# led_ext_board.net
KiCad netlist of a schematic drawn in Altium Designer
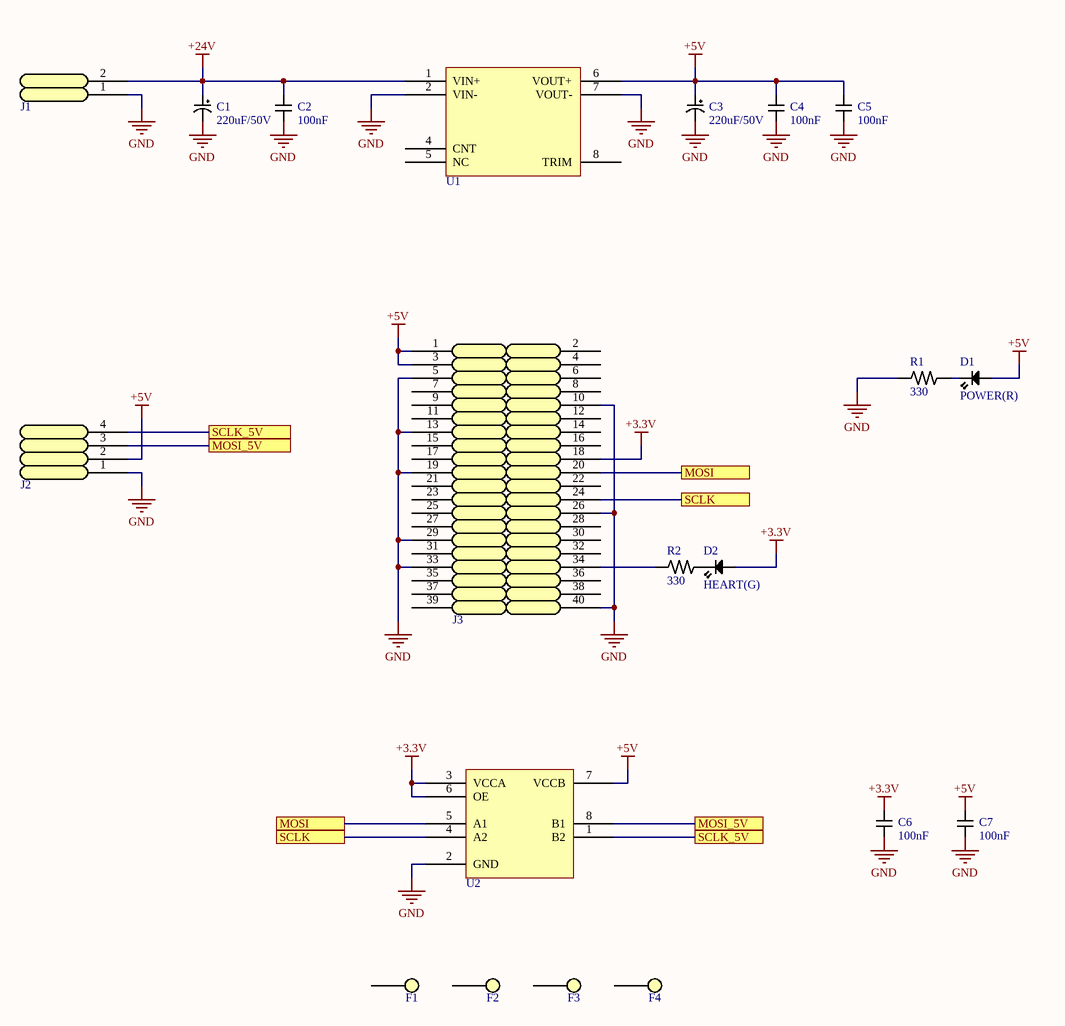
[diagram p0: led_ext_board.SchDoc]

(export (version "E")
  (design (tool "Eeschema 10.0.6"))
  (components
    (comp (ref "C1")
      (value "220uF/50V")
      (footprint "EC-J10-10X10")
      (description "Polarized Capacitor")
      (fields (field (name "Comment") "EC"))
      (libsource (lib "led_ext_board") (part "EC"))
    )
    (comp (ref "C2")
      (value "100nF")
      (footprint "CAP1608L")
      (description "Non-polarized Capacitor")
      (fields (field (name "Comment") "C"))
      (libsource (lib "led_ext_board") (part "C"))
    )
    (comp (ref "C3")
      (value "220uF/50V")
      (footprint "EC-J10-10X10")
      (description "Polarized Capacitor")
      (fields (field (name "Comment") "EC"))
      (libsource (lib "led_ext_board") (part "EC"))
    )
    (comp (ref "C4")
      (value "100nF")
      (footprint "CAP1608L")
      (description "Non-polarized Capacitor")
      (fields (field (name "Comment") "C"))
      (libsource (lib "led_ext_board") (part "C"))
    )
    (comp (ref "C5")
      (value "100nF")
      (footprint "CAP1608L")
      (description "Non-polarized Capacitor")
      (fields (field (name "Comment") "C"))
      (libsource (lib "led_ext_board") (part "C"))
    )
    (comp (ref "C6")
      (value "100nF")
      (footprint "CAP1608L")
      (description "Non-polarized Capacitor")
      (fields (field (name "Comment") "C"))
      (libsource (lib "led_ext_board") (part "C"))
    )
    (comp (ref "C7")
      (value "100nF")
      (footprint "CAP1608L")
      (description "Non-polarized Capacitor")
      (fields (field (name "Comment") "C"))
      (libsource (lib "led_ext_board") (part "C"))
    )
    (comp (ref "D1")
      (value "POWER(R)")
      (footprint "LED1608L")
      (description "Typical LED")
      (fields (field (name "Comment") "LED"))
      (libsource (lib "led_ext_board") (part "LED"))
    )
    (comp (ref "D2")
      (value "HEART(G)")
      (footprint "LED1608L")
      (description "Typical LED")
      (fields (field (name "Comment") "LED"))
      (libsource (lib "led_ext_board") (part "LED"))
    )
    (comp (ref "F1")
      (value "FIXED_HOLE")
      (footprint "FIXED_HOLE_PAD")
      (libsource (lib "led_ext_board") (part "FIXED_HOLE"))
    )
    (comp (ref "F2")
      (value "FIXED_HOLE")
      (footprint "FIXED_HOLE_PAD")
      (libsource (lib "led_ext_board") (part "FIXED_HOLE"))
    )
    (comp (ref "F3")
      (value "FIXED_HOLE")
      (footprint "FIXED_HOLE_PAD")
      (libsource (lib "led_ext_board") (part "FIXED_HOLE"))
    )
    (comp (ref "F4")
      (value "FIXED_HOLE")
      (footprint "FIXED_HOLE_PAD")
      (libsource (lib "led_ext_board") (part "FIXED_HOLE"))
    )
    (comp (ref "J1")
      (value "CON2")
      (footprint "DG128-5.0-02P")
      (libsource (lib "led_ext_board") (part "CON2"))
    )
    (comp (ref "J2")
      (value "CON4")
      (footprint "DG128-5.0-04P")
      (description "Generic Connector 4 Pin")
      (libsource (lib "led_ext_board") (part "CON4"))
    )
    (comp (ref "J3")
      (value "CON2X20")
      (footprint "HS-2X20-2.54-V")
      (description "Generic Connector 2X20")
      (libsource (lib "led_ext_board") (part "CON2X20"))
    )
    (comp (ref "R1")
      (value "330")
      (footprint "RES1608L")
      (description "Resistor")
      (fields (field (name "Comment") "R"))
      (libsource (lib "led_ext_board") (part "R"))
    )
    (comp (ref "R2")
      (value "330")
      (footprint "RES1608L")
      (description "Resistor")
      (fields (field (name "Comment") "R"))
      (libsource (lib "led_ext_board") (part "R"))
    )
    (comp (ref "U1")
      (value "PBR50 Series DC-DC Converter")
      (footprint "PBR50-24-5")
      (libsource (lib "led_ext_board") (part "PBR50"))
    )
    (comp (ref "U2")
      (value "TXB0102")
      (footprint "TXB0102")
      (libsource (lib "led_ext_board") (part "TXB0102"))
    )
  )
  (nets
    (net (code "1") (name "+3.3V") (class "Default")
      (node (ref "C6") (pin "1") (pinfunction "1_1") (pintype "passive"))
      (node (ref "D2") (pin "2") (pinfunction "2_2") (pintype "passive"))
      (node (ref "J3") (pin "18") (pinfunction "18_18") (pintype "passive"))
      (node (ref "U2") (pin "3") (pinfunction "VCCA_3") (pintype "passive"))
      (node (ref "U2") (pin "6") (pinfunction "OE_6") (pintype "passive"))
    )
    (net (code "2") (name "+5V") (class "Default")
      (node (ref "C3") (pin "1") (pinfunction "1_1") (pintype "passive"))
      (node (ref "C4") (pin "1") (pinfunction "1_1") (pintype "passive"))
      (node (ref "C5") (pin "1") (pinfunction "1_1") (pintype "passive"))
      (node (ref "C7") (pin "1") (pinfunction "1_1") (pintype "passive"))
      (node (ref "D1") (pin "2") (pinfunction "2_2") (pintype "passive"))
      (node (ref "J2") (pin "2") (pinfunction "2_2") (pintype "passive"))
      (node (ref "J3") (pin "1") (pinfunction "1_1") (pintype "passive"))
      (node (ref "J3") (pin "3") (pinfunction "3_3") (pintype "passive"))
      (node (ref "U1") (pin "6") (pinfunction "VOUT+_6") (pintype "passive"))
      (node (ref "U2") (pin "7") (pinfunction "VCCB_7") (pintype "passive"))
    )
    (net (code "3") (name "+24V") (class "Default")
      (node (ref "C1") (pin "1") (pinfunction "1_1") (pintype "passive"))
      (node (ref "C2") (pin "1") (pinfunction "1_1") (pintype "passive"))
      (node (ref "J1") (pin "2") (pinfunction "2_2") (pintype "passive"))
      (node (ref "U1") (pin "1") (pinfunction "VIN+_1") (pintype "passive"))
    )
    (net (code "4") (name "/MOSI") (class "Default")
      (node (ref "J3") (pin "20") (pinfunction "20_20") (pintype "passive"))
      (node (ref "U2") (pin "5") (pinfunction "A1_5") (pintype "passive"))
    )
    (net (code "5") (name "/MOSI_5V") (class "Default")
      (node (ref "J2") (pin "3") (pinfunction "3_3") (pintype "passive"))
      (node (ref "U2") (pin "8") (pinfunction "B1_8") (pintype "passive"))
    )
    (net (code "6") (name "/SCLK") (class "Default")
      (node (ref "J3") (pin "24") (pinfunction "24_24") (pintype "passive"))
      (node (ref "U2") (pin "4") (pinfunction "A2_4") (pintype "passive"))
    )
    (net (code "7") (name "/SCLK_5V") (class "Default")
      (node (ref "J2") (pin "4") (pinfunction "4_4") (pintype "passive"))
      (node (ref "U2") (pin "1") (pinfunction "B2_1") (pintype "passive"))
    )
    (net (code "8") (name "GND") (class "Default")
      (node (ref "C1") (pin "2") (pinfunction "2_2") (pintype "passive"))
      (node (ref "C2") (pin "2") (pinfunction "2_2") (pintype "passive"))
      (node (ref "C3") (pin "2") (pinfunction "2_2") (pintype "passive"))
      (node (ref "C4") (pin "2") (pinfunction "2_2") (pintype "passive"))
      (node (ref "C5") (pin "2") (pinfunction "2_2") (pintype "passive"))
      (node (ref "C6") (pin "2") (pinfunction "2_2") (pintype "passive"))
      (node (ref "C7") (pin "2") (pinfunction "2_2") (pintype "passive"))
      (node (ref "J1") (pin "1") (pinfunction "1_1") (pintype "passive"))
      (node (ref "J2") (pin "1") (pinfunction "1_1") (pintype "passive"))
      (node (ref "J3") (pin "10") (pinfunction "10_10") (pintype "passive"))
      (node (ref "J3") (pin "13") (pinfunction "13_13") (pintype "passive"))
      (node (ref "J3") (pin "19") (pinfunction "19_19") (pintype "passive"))
      (node (ref "J3") (pin "26") (pinfunction "26_26") (pintype "passive"))
      (node (ref "J3") (pin "29") (pinfunction "29_29") (pintype "passive"))
      (node (ref "J3") (pin "33") (pinfunction "33_33") (pintype "passive"))
      (node (ref "J3") (pin "40") (pinfunction "40_40") (pintype "passive"))
      (node (ref "J3") (pin "5") (pinfunction "5_5") (pintype "passive"))
      (node (ref "R1") (pin "1") (pinfunction "1_1") (pintype "passive"))
      (node (ref "U1") (pin "2") (pinfunction "VIN-_2") (pintype "passive"))
      (node (ref "U1") (pin "7") (pinfunction "VOUT-_7") (pintype "passive"))
      (node (ref "U2") (pin "2") (pinfunction "GND_2") (pintype "passive"))
    )
    (net (code "9") (name "Net-(D1-Pad1)") (class "Default")
      (node (ref "D1") (pin "1") (pinfunction "1_1") (pintype "passive"))
      (node (ref "R1") (pin "2") (pinfunction "2_2") (pintype "passive"))
    )
    (net (code "10") (name "Net-(J3-Pad34)") (class "Default")
      (node (ref "J3") (pin "34") (pinfunction "34_34") (pintype "passive"))
      (node (ref "R2") (pin "1") (pinfunction "1_1") (pintype "passive"))
    )
    (net (code "11") (name "unconnected-(D2-Pad1)") (class "Default")
      (node (ref "D2") (pin "1") (pinfunction "1_1") (pintype "passive"))
    )
    (net (code "12") (name "unconnected-(F1-Pad1)") (class "Default")
      (node (ref "F1") (pin "1") (pinfunction "1_1") (pintype "passive"))
    )
    (net (code "13") (name "unconnected-(F2-Pad1)") (class "Default")
      (node (ref "F2") (pin "1") (pinfunction "1_1") (pintype "passive"))
    )
    (net (code "14") (name "unconnected-(F3-Pad1)") (class "Default")
      (node (ref "F3") (pin "1") (pinfunction "1_1") (pintype "passive"))
    )
    (net (code "15") (name "unconnected-(F4-Pad1)") (class "Default")
      (node (ref "F4") (pin "1") (pinfunction "1_1") (pintype "passive"))
    )
    (net (code "16") (name "unconnected-(J3-Pad2)") (class "Default")
      (node (ref "J3") (pin "2") (pinfunction "2_2") (pintype "passive"))
    )
    (net (code "17") (name "unconnected-(J3-Pad4)") (class "Default")
      (node (ref "J3") (pin "4") (pinfunction "4_4") (pintype "passive"))
    )
    (net (code "18") (name "unconnected-(J3-Pad6)") (class "Default")
      (node (ref "J3") (pin "6") (pinfunction "6_6") (pintype "passive"))
    )
    (net (code "19") (name "unconnected-(J3-Pad7)") (class "Default")
      (node (ref "J3") (pin "7") (pinfunction "7_7") (pintype "passive"))
    )
    (net (code "20") (name "unconnected-(J3-Pad8)") (class "Default")
      (node (ref "J3") (pin "8") (pinfunction "8_8") (pintype "passive"))
    )
    (net (code "21") (name "unconnected-(J3-Pad9)") (class "Default")
      (node (ref "J3") (pin "9") (pinfunction "9_9") (pintype "passive"))
    )
    (net (code "22") (name "unconnected-(J3-Pad11)") (class "Default")
      (node (ref "J3") (pin "11") (pinfunction "11_11") (pintype "passive"))
    )
    (net (code "23") (name "unconnected-(J3-Pad12)") (class "Default")
      (node (ref "J3") (pin "12") (pinfunction "12_12") (pintype "passive"))
    )
    (net (code "24") (name "unconnected-(J3-Pad14)") (class "Default")
      (node (ref "J3") (pin "14") (pinfunction "14_14") (pintype "passive"))
    )
    (net (code "25") (name "unconnected-(J3-Pad15)") (class "Default")
      (node (ref "J3") (pin "15") (pinfunction "15_15") (pintype "passive"))
    )
    (net (code "26") (name "unconnected-(J3-Pad16)") (class "Default")
      (node (ref "J3") (pin "16") (pinfunction "16_16") (pintype "passive"))
    )
    (net (code "27") (name "unconnected-(J3-Pad17)") (class "Default")
      (node (ref "J3") (pin "17") (pinfunction "17_17") (pintype "passive"))
    )
    (net (code "28") (name "unconnected-(J3-Pad21)") (class "Default")
      (node (ref "J3") (pin "21") (pinfunction "21_21") (pintype "passive"))
    )
    (net (code "29") (name "unconnected-(J3-Pad22)") (class "Default")
      (node (ref "J3") (pin "22") (pinfunction "22_22") (pintype "passive"))
    )
    (net (code "30") (name "unconnected-(J3-Pad23)") (class "Default")
      (node (ref "J3") (pin "23") (pinfunction "23_23") (pintype "passive"))
    )
    (net (code "31") (name "unconnected-(J3-Pad25)") (class "Default")
      (node (ref "J3") (pin "25") (pinfunction "25_25") (pintype "passive"))
    )
    (net (code "32") (name "unconnected-(J3-Pad27)") (class "Default")
      (node (ref "J3") (pin "27") (pinfunction "27_27") (pintype "passive"))
    )
    (net (code "33") (name "unconnected-(J3-Pad28)") (class "Default")
      (node (ref "J3") (pin "28") (pinfunction "28_28") (pintype "passive"))
    )
    (net (code "34") (name "unconnected-(J3-Pad30)") (class "Default")
      (node (ref "J3") (pin "30") (pinfunction "30_30") (pintype "passive"))
    )
    (net (code "35") (name "unconnected-(J3-Pad31)") (class "Default")
      (node (ref "J3") (pin "31") (pinfunction "31_31") (pintype "passive"))
    )
    (net (code "36") (name "unconnected-(J3-Pad32)") (class "Default")
      (node (ref "J3") (pin "32") (pinfunction "32_32") (pintype "passive"))
    )
    (net (code "37") (name "unconnected-(J3-Pad35)") (class "Default")
      (node (ref "J3") (pin "35") (pinfunction "35_35") (pintype "passive"))
    )
    (net (code "38") (name "unconnected-(J3-Pad36)") (class "Default")
      (node (ref "J3") (pin "36") (pinfunction "36_36") (pintype "passive"))
    )
    (net (code "39") (name "unconnected-(J3-Pad37)") (class "Default")
      (node (ref "J3") (pin "37") (pinfunction "37_37") (pintype "passive"))
    )
    (net (code "40") (name "unconnected-(J3-Pad38)") (class "Default")
      (node (ref "J3") (pin "38") (pinfunction "38_38") (pintype "passive"))
    )
    (net (code "41") (name "unconnected-(J3-Pad39)") (class "Default")
      (node (ref "J3") (pin "39") (pinfunction "39_39") (pintype "passive"))
    )
    (net (code "42") (name "unconnected-(R2-Pad2)") (class "Default")
      (node (ref "R2") (pin "2") (pinfunction "2_2") (pintype "passive"))
    )
    (net (code "43") (name "unconnected-(U1-CNT-Pad4)") (class "Default")
      (node (ref "U1") (pin "4") (pinfunction "CNT_4") (pintype "passive"))
    )
    (net (code "44") (name "unconnected-(U1-NC-Pad5)") (class "Default")
      (node (ref "U1") (pin "5") (pinfunction "NC_5") (pintype "passive"))
    )
    (net (code "45") (name "unconnected-(U1-TRIM-Pad8)") (class "Default")
      (node (ref "U1") (pin "8") (pinfunction "TRIM_8") (pintype "passive"))
    )
  )
)
